# mLRS-rx-board01-v014.net
KiCad netlist of a schematic drawn in EAGLE
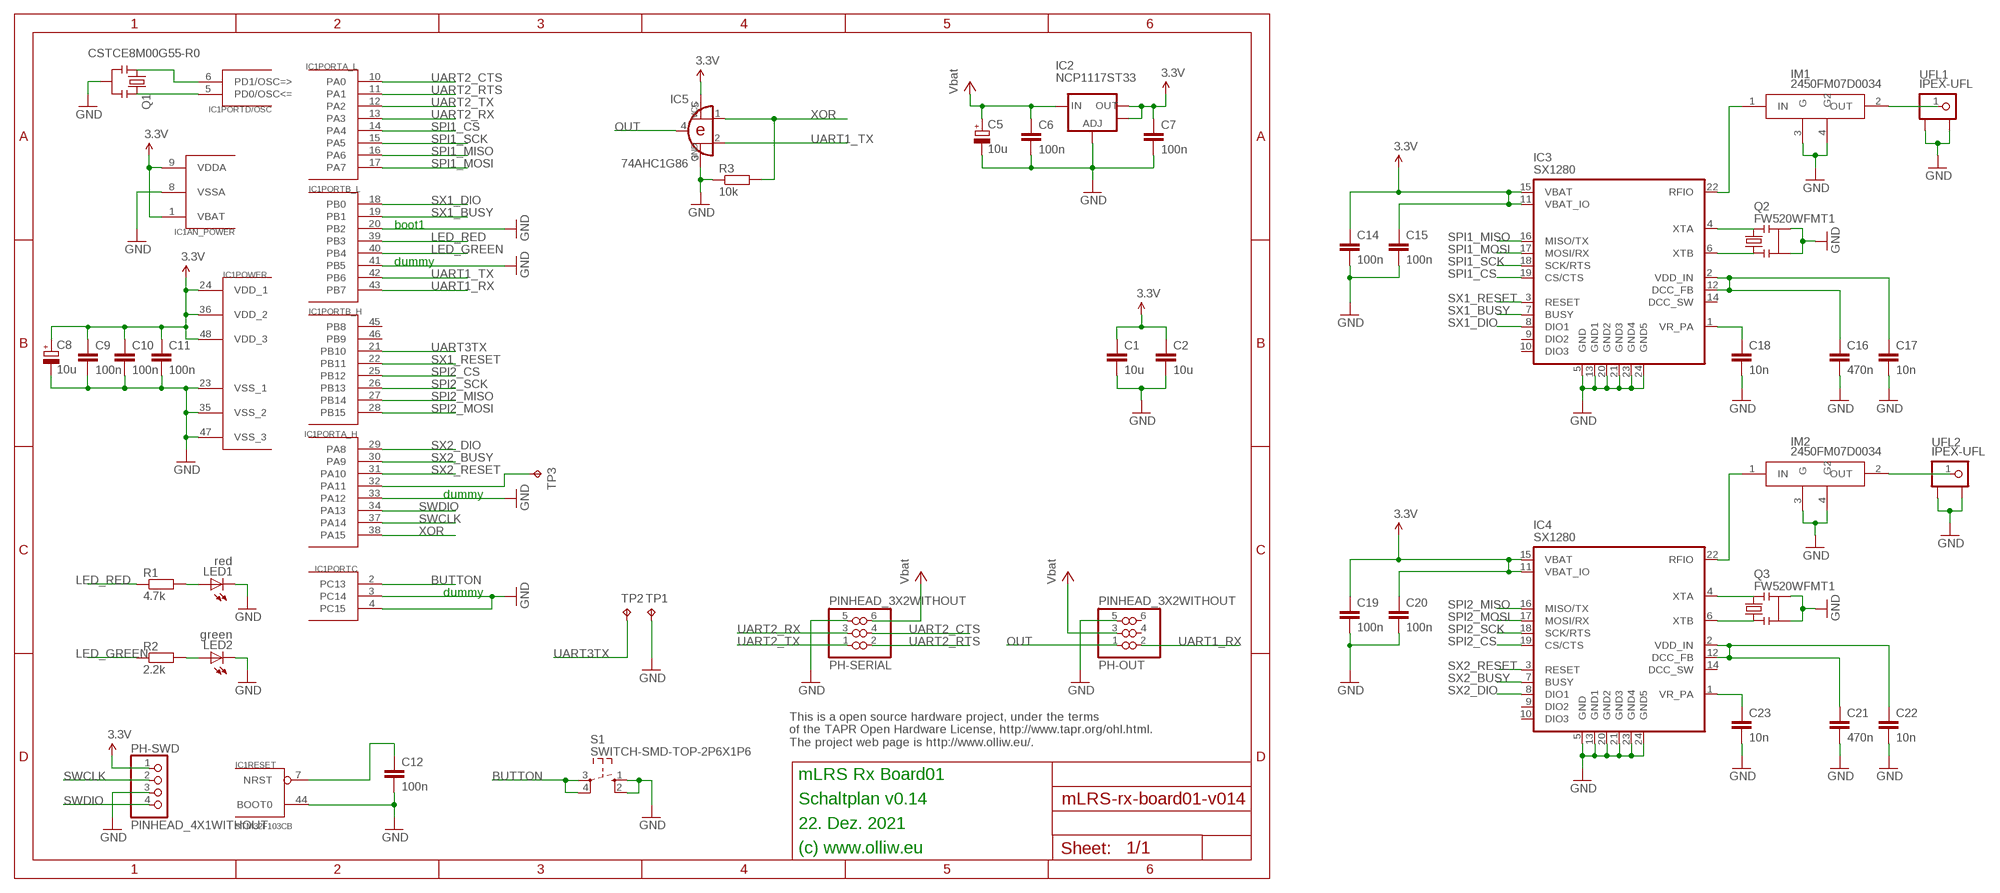
[diagram p0: schematic, sheet 1]

(export (version "E")
  (design (tool "Eeschema 10.0.6"))
  (components
    (comp (ref "C1")
      (value "10u")
      (footprint "eagle-import:C0603")
      (libsource (lib "eagle-import") (part "C-EUC0603"))
    )
    (comp (ref "C2")
      (value "10u")
      (footprint "eagle-import:C0603")
      (libsource (lib "eagle-import") (part "C-EUC0603"))
    )
    (comp (ref "C5")
      (value "10u")
      (footprint "eagle-import:SMC_A")
      (libsource (lib "eagle-import") (part "CPOL-EUSMCA"))
    )
    (comp (ref "C6")
      (value "100n")
      (footprint "eagle-import:C0603")
      (libsource (lib "eagle-import") (part "C-EUC0603"))
    )
    (comp (ref "C7")
      (value "100n")
      (footprint "eagle-import:C0603")
      (libsource (lib "eagle-import") (part "C-EUC0603"))
    )
    (comp (ref "C8")
      (value "10u")
      (footprint "eagle-import:SMC_A")
      (libsource (lib "eagle-import") (part "CPOL-EUSMCA"))
    )
    (comp (ref "C9")
      (value "100n")
      (footprint "eagle-import:C0603")
      (libsource (lib "eagle-import") (part "C-EUC0603"))
    )
    (comp (ref "C10")
      (value "100n")
      (footprint "eagle-import:C0603")
      (libsource (lib "eagle-import") (part "C-EUC0603"))
    )
    (comp (ref "C11")
      (value "100n")
      (footprint "eagle-import:C0603")
      (libsource (lib "eagle-import") (part "C-EUC0603"))
    )
    (comp (ref "C12")
      (value "100n")
      (footprint "eagle-import:C0603")
      (libsource (lib "eagle-import") (part "C-EUC0603"))
    )
    (comp (ref "C14")
      (value "100n")
      (footprint "eagle-import:C0402")
      (libsource (lib "eagle-import") (part "C-EUC0402"))
    )
    (comp (ref "C15")
      (value "100n")
      (footprint "eagle-import:C0402")
      (libsource (lib "eagle-import") (part "C-EUC0402"))
    )
    (comp (ref "C16")
      (value "470n")
      (footprint "eagle-import:C0402")
      (libsource (lib "eagle-import") (part "C-EUC0402"))
    )
    (comp (ref "C17")
      (value "10n")
      (footprint "eagle-import:C0402")
      (libsource (lib "eagle-import") (part "C-EUC0402"))
    )
    (comp (ref "C18")
      (value "10n")
      (footprint "eagle-import:C0402")
      (libsource (lib "eagle-import") (part "C-EUC0402"))
    )
    (comp (ref "C19")
      (value "100n")
      (footprint "eagle-import:C0402")
      (libsource (lib "eagle-import") (part "C-EUC0402"))
    )
    (comp (ref "C20")
      (value "100n")
      (footprint "eagle-import:C0402")
      (libsource (lib "eagle-import") (part "C-EUC0402"))
    )
    (comp (ref "C21")
      (value "470n")
      (footprint "eagle-import:C0402")
      (libsource (lib "eagle-import") (part "C-EUC0402"))
    )
    (comp (ref "C22")
      (value "10n")
      (footprint "eagle-import:C0402")
      (libsource (lib "eagle-import") (part "C-EUC0402"))
    )
    (comp (ref "C23")
      (value "10n")
      (footprint "eagle-import:C0402")
      (libsource (lib "eagle-import") (part "C-EUC0402"))
    )
    (comp (ref "IC1")
      (value "STM32F103CB")
      (footprint "eagle-import:TQFP48")
      (libsource (lib "eagle-import") (part "STM32F10XCXT6"))
    )
    (comp (ref "IC2")
      (value "NCP1117ST33")
      (footprint "eagle-import:SOT223")
      (libsource (lib "eagle-import") (part "V_REG_LM1117SOT223"))
    )
    (comp (ref "IC3")
      (value "SX1280")
      (footprint "eagle-import:QFN24-4X4-SX128X")
      (libsource (lib "eagle-import") (part "SX1280"))
    )
    (comp (ref "IC4")
      (value "SX1280")
      (footprint "eagle-import:QFN24-4X4-SX128X")
      (libsource (lib "eagle-import") (part "SX1280"))
    )
    (comp (ref "IC5")
      (value "74AHC1G86")
      (footprint "eagle-import:SOT23-5-VER1")
      (libsource (lib "eagle-import") (part "74AHC1G86"))
    )
    (comp (ref "IM1")
      (value "2450FM07D0034")
      (footprint "eagle-import:SX-IMPEDANCE-MATCH")
      (libsource (lib "eagle-import") (part "SX-IMPEDANCE-MATCH"))
    )
    (comp (ref "IM2")
      (value "2450FM07D0034")
      (footprint "eagle-import:SX-IMPEDANCE-MATCH")
      (libsource (lib "eagle-import") (part "SX-IMPEDANCE-MATCH"))
    )
    (comp (ref "LED1")
      (value "red")
      (footprint "eagle-import:CHIPLED_0603")
      (libsource (lib "eagle-import") (part "LEDCHIPLED_0603"))
    )
    (comp (ref "LED2")
      (value "green")
      (footprint "eagle-import:CHIPLED_0603")
      (libsource (lib "eagle-import") (part "LEDCHIPLED_0603"))
    )
    (comp (ref "PH-OUT")
      (value "PINHEAD_3X2WITHOUT")
      (footprint "eagle-import:PINHEAD_3X2_WO")
      (libsource (lib "eagle-import") (part "PINHEAD_3X2WITHOUT"))
    )
    (comp (ref "PH-SERIAL")
      (value "PINHEAD_3X2WITHOUT")
      (footprint "eagle-import:PINHEAD_3X2_WO")
      (libsource (lib "eagle-import") (part "PINHEAD_3X2WITHOUT"))
    )
    (comp (ref "PH-SWD")
      (value "PINHEAD_4X1WITHOUT")
      (footprint "eagle-import:PINHEAD_4X1_WO")
      (libsource (lib "eagle-import") (part "PINHEAD_4X1WITHOUT"))
    )
    (comp (ref "Q1")
      (value "CSTCE8M00G55-R0")
      (footprint "eagle-import:RESONATOR-SMD")
      (libsource (lib "eagle-import") (part "RESONATORSMD"))
    )
    (comp (ref "Q2")
      (value "FW520WFMT1")
      (footprint "eagle-import:CRYSTAL-SMD-2X1P6-GND")
      (libsource (lib "eagle-import") (part "CRYSTAL52MHZ"))
    )
    (comp (ref "Q3")
      (value "FW520WFMT1")
      (footprint "eagle-import:CRYSTAL-SMD-2X1P6-GND")
      (libsource (lib "eagle-import") (part "CRYSTAL52MHZ"))
    )
    (comp (ref "R1")
      (value "4.7k")
      (footprint "eagle-import:R0402")
      (libsource (lib "eagle-import") (part "R-EU_R0402"))
    )
    (comp (ref "R2")
      (value "2.2k")
      (footprint "eagle-import:R0402")
      (libsource (lib "eagle-import") (part "R-EU_R0402"))
    )
    (comp (ref "R3")
      (value "10k")
      (footprint "eagle-import:R0402")
      (libsource (lib "eagle-import") (part "R-EU_R0402"))
    )
    (comp (ref "S1")
      (value "SWITCH-SMD-TOP-2P6X1P6")
      (footprint "eagle-import:TACTILE-SWITCH-SMD-TOP-2P6X1X6")
      (libsource (lib "eagle-import") (part "SWITCH-SMD-TOP-2P6X1P6"))
    )
    (comp (ref "TP1")
      (value "TPB1,27")
      (footprint "eagle-import:B1,27")
      (libsource (lib "eagle-import") (part "TPB1,27"))
    )
    (comp (ref "TP2")
      (value "TPB1,27")
      (footprint "eagle-import:B1,27")
      (libsource (lib "eagle-import") (part "TPB1,27"))
    )
    (comp (ref "TP3")
      (value "TPTP08R")
      (footprint "eagle-import:TP08R")
      (libsource (lib "eagle-import") (part "TPTP08R"))
    )
    (comp (ref "UFL1")
      (value "IPEX-UFL")
      (footprint "eagle-import:IPEX-UFL-SMD")
      (libsource (lib "eagle-import") (part "IPEX-UFL"))
    )
    (comp (ref "UFL2")
      (value "IPEX-UFL")
      (footprint "eagle-import:IPEX-UFL-SMD")
      (libsource (lib "eagle-import") (part "IPEX-UFL"))
    )
  )
  (nets
    (net (code "1") (name "/BUTTON") (class "Default")
      (node (ref "IC1") (pin "2") (pinfunction "PC13_2") (pintype "bidirectional"))
      (node (ref "S1") (pin "3") (pinfunction "3_3") (pintype "passive"))
      (node (ref "S1") (pin "4") (pinfunction "4_4") (pintype "passive"))
    )
    (net (code "2") (name "/LED_GREEN") (class "Default")
      (node (ref "IC1") (pin "40") (pinfunction "PB4_40") (pintype "bidirectional"))
      (node (ref "R2") (pin "1") (pinfunction "1_1") (pintype "passive"))
    )
    (net (code "3") (name "/LED_RED") (class "Default")
      (node (ref "IC1") (pin "39") (pinfunction "PB3_39") (pintype "bidirectional"))
      (node (ref "R1") (pin "1") (pinfunction "1_1") (pintype "passive"))
    )
    (net (code "4") (name "/OUT") (class "Default")
      (node (ref "IC5") (pin "4") (pinfunction "O_4") (pintype "output"))
      (node (ref "PH-OUT") (pin "1") (pinfunction "1_1") (pintype "passive"))
    )
    (net (code "5") (name "/SPI1_CS") (class "Default")
      (node (ref "IC1") (pin "14") (pinfunction "PA4_14") (pintype "bidirectional"))
      (node (ref "IC3") (pin "19") (pinfunction "CS/CTS_19") (pintype "input"))
    )
    (net (code "6") (name "/SPI1_MISO") (class "Default")
      (node (ref "IC1") (pin "16") (pinfunction "PA6_16") (pintype "bidirectional"))
      (node (ref "IC3") (pin "16") (pinfunction "MISO/TX_16") (pintype "input"))
    )
    (net (code "7") (name "/SPI1_MOSI") (class "Default")
      (node (ref "IC1") (pin "17") (pinfunction "PA7_17") (pintype "bidirectional"))
      (node (ref "IC3") (pin "17") (pinfunction "MOSI/RX_17") (pintype "input"))
    )
    (net (code "8") (name "/SPI1_SCK") (class "Default")
      (node (ref "IC1") (pin "15") (pinfunction "PA5_15") (pintype "bidirectional"))
      (node (ref "IC3") (pin "18") (pinfunction "SCK/RTS_18") (pintype "input"))
    )
    (net (code "9") (name "/SPI2_CS") (class "Default")
      (node (ref "IC1") (pin "25") (pinfunction "PB12_25") (pintype "bidirectional"))
      (node (ref "IC4") (pin "19") (pinfunction "CS/CTS_19") (pintype "input"))
    )
    (net (code "10") (name "/SPI2_MISO") (class "Default")
      (node (ref "IC1") (pin "27") (pinfunction "PB14_27") (pintype "bidirectional"))
      (node (ref "IC4") (pin "16") (pinfunction "MISO/TX_16") (pintype "input"))
    )
    (net (code "11") (name "/SPI2_MOSI") (class "Default")
      (node (ref "IC1") (pin "28") (pinfunction "PB15_28") (pintype "bidirectional"))
      (node (ref "IC4") (pin "17") (pinfunction "MOSI/RX_17") (pintype "input"))
    )
    (net (code "12") (name "/SPI2_SCK") (class "Default")
      (node (ref "IC1") (pin "26") (pinfunction "PB13_26") (pintype "bidirectional"))
      (node (ref "IC4") (pin "18") (pinfunction "SCK/RTS_18") (pintype "input"))
    )
    (net (code "13") (name "/SWCLK") (class "Default")
      (node (ref "IC1") (pin "37") (pinfunction "PA14_37") (pintype "bidirectional"))
      (node (ref "PH-SWD") (pin "2") (pinfunction "2_2") (pintype "passive"))
    )
    (net (code "14") (name "/SWDIO") (class "Default")
      (node (ref "IC1") (pin "34") (pinfunction "PA13_34") (pintype "bidirectional"))
      (node (ref "PH-SWD") (pin "4") (pinfunction "4_4") (pintype "passive"))
    )
    (net (code "15") (name "/SX1_BUSY") (class "Default")
      (node (ref "IC1") (pin "19") (pinfunction "PB1_19") (pintype "bidirectional"))
      (node (ref "IC3") (pin "7") (pinfunction "BUSY_7") (pintype "bidirectional"))
    )
    (net (code "16") (name "/SX1_DIO") (class "Default")
      (node (ref "IC1") (pin "18") (pinfunction "PB0_18") (pintype "bidirectional"))
      (node (ref "IC3") (pin "8") (pinfunction "DIO1_8") (pintype "input"))
    )
    (net (code "17") (name "/SX1_RESET") (class "Default")
      (node (ref "IC1") (pin "22") (pinfunction "PB11_22") (pintype "bidirectional"))
      (node (ref "IC3") (pin "3") (pinfunction "RESET_3") (pintype "bidirectional"))
    )
    (net (code "18") (name "/SX2_BUSY") (class "Default")
      (node (ref "IC1") (pin "30") (pinfunction "PA9_30") (pintype "bidirectional"))
      (node (ref "IC4") (pin "7") (pinfunction "BUSY_7") (pintype "bidirectional"))
    )
    (net (code "19") (name "/SX2_DIO") (class "Default")
      (node (ref "IC1") (pin "29") (pinfunction "PA8_29") (pintype "bidirectional"))
      (node (ref "IC4") (pin "8") (pinfunction "DIO1_8") (pintype "input"))
    )
    (net (code "20") (name "/SX2_RESET") (class "Default")
      (node (ref "IC1") (pin "31") (pinfunction "PA10_31") (pintype "bidirectional"))
      (node (ref "IC4") (pin "3") (pinfunction "RESET_3") (pintype "bidirectional"))
    )
    (net (code "21") (name "/UART1_RX") (class "Default")
      (node (ref "IC1") (pin "43") (pinfunction "PB7_43") (pintype "bidirectional"))
      (node (ref "PH-OUT") (pin "2") (pinfunction "2_2") (pintype "passive"))
    )
    (net (code "22") (name "/UART1_TX") (class "Default")
      (node (ref "IC1") (pin "42") (pinfunction "PB6_42") (pintype "bidirectional"))
      (node (ref "IC5") (pin "2") (pinfunction "I1_2") (pintype "input"))
    )
    (net (code "23") (name "/UART2_CTS") (class "Default")
      (node (ref "IC1") (pin "10") (pinfunction "PA0_10") (pintype "bidirectional"))
      (node (ref "PH-SERIAL") (pin "4") (pinfunction "4_4") (pintype "passive"))
    )
    (net (code "24") (name "/UART2_RTS") (class "Default")
      (node (ref "IC1") (pin "11") (pinfunction "PA1_11") (pintype "bidirectional"))
      (node (ref "PH-SERIAL") (pin "2") (pinfunction "2_2") (pintype "passive"))
    )
    (net (code "25") (name "/UART2_RX") (class "Default")
      (node (ref "IC1") (pin "13") (pinfunction "PA3_13") (pintype "bidirectional"))
      (node (ref "PH-SERIAL") (pin "3") (pinfunction "3_3") (pintype "passive"))
    )
    (net (code "26") (name "/UART2_TX") (class "Default")
      (node (ref "IC1") (pin "12") (pinfunction "PA2_12") (pintype "bidirectional"))
      (node (ref "PH-SERIAL") (pin "1") (pinfunction "1_1") (pintype "passive"))
    )
    (net (code "27") (name "/UART3TX") (class "Default")
      (node (ref "IC1") (pin "21") (pinfunction "PB10_21") (pintype "bidirectional"))
      (node (ref "TP2") (pin "TP") (pinfunction "TP_TP") (pintype "input"))
    )
    (net (code "28") (name "/XOR") (class "Default")
      (node (ref "IC1") (pin "38") (pinfunction "PA15_38") (pintype "bidirectional"))
      (node (ref "IC5") (pin "1") (pinfunction "I0_1") (pintype "input"))
      (node (ref "R3") (pin "2") (pinfunction "2_2") (pintype "passive"))
    )
    (net (code "29") (name "3.3V") (class "Default")
      (node (ref "C1") (pin "1") (pinfunction "1_1") (pintype "passive"))
      (node (ref "C10") (pin "1") (pinfunction "1_1") (pintype "passive"))
      (node (ref "C11") (pin "1") (pinfunction "1_1") (pintype "passive"))
      (node (ref "C14") (pin "1") (pinfunction "1_1") (pintype "passive"))
      (node (ref "C15") (pin "1") (pinfunction "1_1") (pintype "passive"))
      (node (ref "C19") (pin "1") (pinfunction "1_1") (pintype "passive"))
      (node (ref "C2") (pin "1") (pinfunction "1_1") (pintype "passive"))
      (node (ref "C20") (pin "1") (pinfunction "1_1") (pintype "passive"))
      (node (ref "C7") (pin "1") (pinfunction "1_1") (pintype "passive"))
      (node (ref "C8") (pin "+") (pinfunction "+_+") (pintype "passive"))
      (node (ref "C9") (pin "1") (pinfunction "1_1") (pintype "passive"))
      (node (ref "IC1") (pin "1") (pinfunction "VBAT_1") (pintype "power_in"))
      (node (ref "IC1") (pin "24") (pinfunction "VDD_1_24") (pintype "power_in"))
      (node (ref "IC1") (pin "36") (pinfunction "VDD_2_36") (pintype "power_in"))
      (node (ref "IC1") (pin "48") (pinfunction "VDD_3_48") (pintype "power_in"))
      (node (ref "IC1") (pin "9") (pinfunction "VDDA_9") (pintype "power_in"))
      (node (ref "IC2") (pin "2") (pinfunction "OUT_2") (pintype "output"))
      (node (ref "IC2") (pin "4") (pinfunction "OUT_4") (pintype "output"))
      (node (ref "IC3") (pin "11") (pinfunction "VBAT_IO_11") (pintype "power_in"))
      (node (ref "IC3") (pin "15") (pinfunction "VBAT_15") (pintype "power_in"))
      (node (ref "IC4") (pin "11") (pinfunction "VBAT_IO_11") (pintype "power_in"))
      (node (ref "IC4") (pin "15") (pinfunction "VBAT_15") (pintype "power_in"))
      (node (ref "IC5") (pin "5") (pinfunction "VCC_5") (pintype "power_in"))
      (node (ref "PH-SWD") (pin "1") (pinfunction "1_1") (pintype "passive"))
    )
    (net (code "30") (name "GND") (class "Default")
      (node (ref "C1") (pin "2") (pinfunction "2_2") (pintype "passive"))
      (node (ref "C10") (pin "2") (pinfunction "2_2") (pintype "passive"))
      (node (ref "C11") (pin "2") (pinfunction "2_2") (pintype "passive"))
      (node (ref "C12") (pin "2") (pinfunction "2_2") (pintype "passive"))
      (node (ref "C14") (pin "2") (pinfunction "2_2") (pintype "passive"))
      (node (ref "C15") (pin "2") (pinfunction "2_2") (pintype "passive"))
      (node (ref "C16") (pin "2") (pinfunction "2_2") (pintype "passive"))
      (node (ref "C17") (pin "2") (pinfunction "2_2") (pintype "passive"))
      (node (ref "C18") (pin "2") (pinfunction "2_2") (pintype "passive"))
      (node (ref "C19") (pin "2") (pinfunction "2_2") (pintype "passive"))
      (node (ref "C2") (pin "2") (pinfunction "2_2") (pintype "passive"))
      (node (ref "C20") (pin "2") (pinfunction "2_2") (pintype "passive"))
      (node (ref "C21") (pin "2") (pinfunction "2_2") (pintype "passive"))
      (node (ref "C22") (pin "2") (pinfunction "2_2") (pintype "passive"))
      (node (ref "C23") (pin "2") (pinfunction "2_2") (pintype "passive"))
      (node (ref "C5") (pin "-") (pinfunction "-_-") (pintype "passive"))
      (node (ref "C6") (pin "2") (pinfunction "2_2") (pintype "passive"))
      (node (ref "C7") (pin "2") (pinfunction "2_2") (pintype "passive"))
      (node (ref "C8") (pin "-") (pinfunction "-_-") (pintype "passive"))
      (node (ref "C9") (pin "2") (pinfunction "2_2") (pintype "passive"))
      (node (ref "IC1") (pin "20") (pinfunction "PB2_20") (pintype "bidirectional"))
      (node (ref "IC1") (pin "23") (pinfunction "VSS_1_23") (pintype "power_in"))
      (node (ref "IC1") (pin "3") (pinfunction "PC14_3") (pintype "bidirectional"))
      (node (ref "IC1") (pin "33") (pinfunction "PA12_33") (pintype "bidirectional"))
      (node (ref "IC1") (pin "35") (pinfunction "VSS_2_35") (pintype "power_in"))
      (node (ref "IC1") (pin "4") (pinfunction "PC15_4") (pintype "bidirectional"))
      (node (ref "IC1") (pin "41") (pinfunction "PB5_41") (pintype "bidirectional"))
      (node (ref "IC1") (pin "44") (pinfunction "BOOT0_44") (pintype "input"))
      (node (ref "IC1") (pin "47") (pinfunction "VSS_3_47") (pintype "power_in"))
      (node (ref "IC1") (pin "8") (pinfunction "VSSA_8") (pintype "power_in"))
      (node (ref "IC2") (pin "1") (pinfunction "ADJ_1") (pintype "input"))
      (node (ref "IC3") (pin "13") (pinfunction "GND1_13") (pintype "power_in"))
      (node (ref "IC3") (pin "20") (pinfunction "GND2_20") (pintype "power_in"))
      (node (ref "IC3") (pin "21") (pinfunction "GND3_21") (pintype "power_in"))
      (node (ref "IC3") (pin "23") (pinfunction "GND4_23") (pintype "power_in"))
      (node (ref "IC3") (pin "24") (pinfunction "GND5_24") (pintype "power_in"))
      (node (ref "IC3") (pin "5") (pinfunction "GND_5") (pintype "power_in"))
      (node (ref "IC4") (pin "13") (pinfunction "GND1_13") (pintype "power_in"))
      (node (ref "IC4") (pin "20") (pinfunction "GND2_20") (pintype "power_in"))
      (node (ref "IC4") (pin "21") (pinfunction "GND3_21") (pintype "power_in"))
      (node (ref "IC4") (pin "23") (pinfunction "GND4_23") (pintype "power_in"))
      (node (ref "IC4") (pin "24") (pinfunction "GND5_24") (pintype "power_in"))
      (node (ref "IC4") (pin "5") (pinfunction "GND_5") (pintype "power_in"))
      (node (ref "IC5") (pin "3") (pinfunction "GND_3") (pintype "power_in"))
      (node (ref "IM1") (pin "3") (pinfunction "G_3") (pintype "power_in"))
      (node (ref "IM1") (pin "4") (pinfunction "G2_4") (pintype "power_in"))
      (node (ref "IM2") (pin "3") (pinfunction "G_3") (pintype "power_in"))
      (node (ref "IM2") (pin "4") (pinfunction "G2_4") (pintype "power_in"))
      (node (ref "LED1") (pin "C") (pinfunction "C_C") (pintype "passive"))
      (node (ref "LED2") (pin "C") (pinfunction "C_C") (pintype "passive"))
      (node (ref "PH-OUT") (pin "5") (pinfunction "5_5") (pintype "passive"))
      (node (ref "PH-SERIAL") (pin "5") (pinfunction "5_5") (pintype "passive"))
      (node (ref "PH-SWD") (pin "3") (pinfunction "3_3") (pintype "passive"))
      (node (ref "Q1") (pin "2") (pinfunction "2_2") (pintype "passive"))
      (node (ref "Q2") (pin "2") (pinfunction "2_2") (pintype "passive"))
      (node (ref "Q2") (pin "4") (pinfunction "4_4") (pintype "passive"))
      (node (ref "Q3") (pin "2") (pinfunction "2_2") (pintype "passive"))
      (node (ref "Q3") (pin "4") (pinfunction "4_4") (pintype "passive"))
      (node (ref "R3") (pin "1") (pinfunction "1_1") (pintype "passive"))
      (node (ref "S1") (pin "1") (pinfunction "1_1") (pintype "passive"))
      (node (ref "S1") (pin "2") (pinfunction "2_2") (pintype "passive"))
      (node (ref "TP1") (pin "TP") (pinfunction "TP_TP") (pintype "input"))
      (node (ref "UFL1") (pin "2") (pinfunction "2_2") (pintype "power_in"))
      (node (ref "UFL1") (pin "3") (pinfunction "3_3") (pintype "power_in"))
      (node (ref "UFL2") (pin "2") (pinfunction "2_2") (pintype "power_in"))
      (node (ref "UFL2") (pin "3") (pinfunction "3_3") (pintype "power_in"))
    )
    (net (code "31") (name "Net-(IC1B-PA11)") (class "Default")
      (node (ref "IC1") (pin "32") (pinfunction "PA11_32") (pintype "bidirectional"))
      (node (ref "TP3") (pin "TP") (pinfunction "TP_TP") (pintype "input"))
    )
    (net (code "32") (name "Net-(IC1G-PD0{slash}OSC<=)") (class "Default")
      (node (ref "IC1") (pin "5") (pinfunction "PD0/OSC<=_5") (pintype "bidirectional"))
      (node (ref "Q1") (pin "3") (pinfunction "3_3") (pintype "passive"))
    )
    (net (code "33") (name "Net-(IC1G-PD1{slash}OSC=>)") (class "Default")
      (node (ref "IC1") (pin "6") (pinfunction "PD1/OSC=>_6") (pintype "bidirectional"))
      (node (ref "Q1") (pin "1") (pinfunction "1_1") (pintype "passive"))
    )
    (net (code "34") (name "Net-(IC1I-NRST)") (class "Default")
      (node (ref "C12") (pin "1") (pinfunction "1_1") (pintype "passive"))
      (node (ref "IC1") (pin "7") (pinfunction "NRST_7") (pintype "input"))
    )
    (net (code "35") (name "Net-(IC3-DCC_FB)") (class "Default")
      (node (ref "C16") (pin "1") (pinfunction "1_1") (pintype "passive"))
      (node (ref "C17") (pin "1") (pinfunction "1_1") (pintype "passive"))
      (node (ref "IC3") (pin "12") (pinfunction "DCC_FB_12") (pintype "bidirectional"))
      (node (ref "IC3") (pin "2") (pinfunction "VDD_IN_2") (pintype "power_in"))
    )
    (net (code "36") (name "Net-(IC3-RFIO)") (class "Default")
      (node (ref "IC3") (pin "22") (pinfunction "RFIO_22") (pintype "bidirectional"))
      (node (ref "IM1") (pin "1") (pinfunction "IN_1") (pintype "bidirectional"))
    )
    (net (code "37") (name "Net-(IC3-VR_PA)") (class "Default")
      (node (ref "C18") (pin "1") (pinfunction "1_1") (pintype "passive"))
      (node (ref "IC3") (pin "1") (pinfunction "VR_PA_1") (pintype "bidirectional"))
    )
    (net (code "38") (name "Net-(IC3-XTA)") (class "Default")
      (node (ref "IC3") (pin "4") (pinfunction "XTA_4") (pintype "bidirectional"))
      (node (ref "Q2") (pin "3") (pinfunction "3_3") (pintype "passive"))
    )
    (net (code "39") (name "Net-(IC3-XTB)") (class "Default")
      (node (ref "IC3") (pin "6") (pinfunction "XTB_6") (pintype "bidirectional"))
      (node (ref "Q2") (pin "1") (pinfunction "1_1") (pintype "passive"))
    )
    (net (code "40") (name "Net-(IC4-DCC_FB)") (class "Default")
      (node (ref "C21") (pin "1") (pinfunction "1_1") (pintype "passive"))
      (node (ref "C22") (pin "1") (pinfunction "1_1") (pintype "passive"))
      (node (ref "IC4") (pin "12") (pinfunction "DCC_FB_12") (pintype "bidirectional"))
      (node (ref "IC4") (pin "2") (pinfunction "VDD_IN_2") (pintype "power_in"))
    )
    (net (code "41") (name "Net-(IC4-RFIO)") (class "Default")
      (node (ref "IC4") (pin "22") (pinfunction "RFIO_22") (pintype "bidirectional"))
      (node (ref "IM2") (pin "1") (pinfunction "IN_1") (pintype "bidirectional"))
    )
    (net (code "42") (name "Net-(IC4-VR_PA)") (class "Default")
      (node (ref "C23") (pin "1") (pinfunction "1_1") (pintype "passive"))
      (node (ref "IC4") (pin "1") (pinfunction "VR_PA_1") (pintype "bidirectional"))
    )
    (net (code "43") (name "Net-(IC4-XTA)") (class "Default")
      (node (ref "IC4") (pin "4") (pinfunction "XTA_4") (pintype "bidirectional"))
      (node (ref "Q3") (pin "3") (pinfunction "3_3") (pintype "passive"))
    )
    (net (code "44") (name "Net-(IC4-XTB)") (class "Default")
      (node (ref "IC4") (pin "6") (pinfunction "XTB_6") (pintype "bidirectional"))
      (node (ref "Q3") (pin "1") (pinfunction "1_1") (pintype "passive"))
    )
    (net (code "45") (name "Net-(IM1-OUT)") (class "Default")
      (node (ref "IM1") (pin "2") (pinfunction "OUT_2") (pintype "bidirectional"))
      (node (ref "UFL1") (pin "1") (pinfunction "1_1") (pintype "passive"))
    )
    (net (code "46") (name "Net-(IM2-OUT)") (class "Default")
      (node (ref "IM2") (pin "2") (pinfunction "OUT_2") (pintype "bidirectional"))
      (node (ref "UFL2") (pin "1") (pinfunction "1_1") (pintype "passive"))
    )
    (net (code "47") (name "Net-(LED1-PadA)") (class "Default")
      (node (ref "LED1") (pin "A") (pinfunction "A_A") (pintype "passive"))
      (node (ref "R1") (pin "2") (pinfunction "2_2") (pintype "passive"))
    )
    (net (code "48") (name "Net-(LED2-PadA)") (class "Default")
      (node (ref "LED2") (pin "A") (pinfunction "A_A") (pintype "passive"))
      (node (ref "R2") (pin "2") (pinfunction "2_2") (pintype "passive"))
    )
    (net (code "49") (name "Vbat") (class "Default")
      (node (ref "C5") (pin "+") (pinfunction "+_+") (pintype "passive"))
      (node (ref "C6") (pin "1") (pinfunction "1_1") (pintype "passive"))
      (node (ref "IC2") (pin "3") (pinfunction "IN_3") (pintype "input"))
      (node (ref "PH-OUT") (pin "3") (pinfunction "3_3") (pintype "passive"))
      (node (ref "PH-SERIAL") (pin "6") (pinfunction "6_6") (pintype "passive"))
    )
    (net (code "50") (name "unconnected-(IC1D-PB8-Pad45)") (class "Default")
      (node (ref "IC1") (pin "45") (pinfunction "PB8_45") (pintype "bidirectional"))
    )
    (net (code "51") (name "unconnected-(IC1D-PB9-Pad46)") (class "Default")
      (node (ref "IC1") (pin "46") (pinfunction "PB9_46") (pintype "bidirectional"))
    )
    (net (code "52") (name "unconnected-(IC3-DCC_SW-Pad14)") (class "Default")
      (node (ref "IC3") (pin "14") (pinfunction "DCC_SW_14") (pintype "bidirectional"))
    )
    (net (code "53") (name "unconnected-(IC3-DIO2-Pad9)") (class "Default")
      (node (ref "IC3") (pin "9") (pinfunction "DIO2_9") (pintype "input"))
    )
    (net (code "54") (name "unconnected-(IC3-DIO3-Pad10)") (class "Default")
      (node (ref "IC3") (pin "10") (pinfunction "DIO3_10") (pintype "input"))
    )
    (net (code "55") (name "unconnected-(IC4-DCC_SW-Pad14)") (class "Default")
      (node (ref "IC4") (pin "14") (pinfunction "DCC_SW_14") (pintype "bidirectional"))
    )
    (net (code "56") (name "unconnected-(IC4-DIO2-Pad9)") (class "Default")
      (node (ref "IC4") (pin "9") (pinfunction "DIO2_9") (pintype "input"))
    )
    (net (code "57") (name "unconnected-(IC4-DIO3-Pad10)") (class "Default")
      (node (ref "IC4") (pin "10") (pinfunction "DIO3_10") (pintype "input"))
    )
    (net (code "58") (name "unconnected-(PH-OUT-Pad4)") (class "Default")
      (node (ref "PH-OUT") (pin "4") (pinfunction "4_4") (pintype "passive"))
    )
    (net (code "59") (name "unconnected-(PH-OUT-Pad6)") (class "Default")
      (node (ref "PH-OUT") (pin "6") (pinfunction "6_6") (pintype "passive"))
    )
  )
)
